# MPU6050.net
KiCad netlist of a schematic drawn in Altium Designer
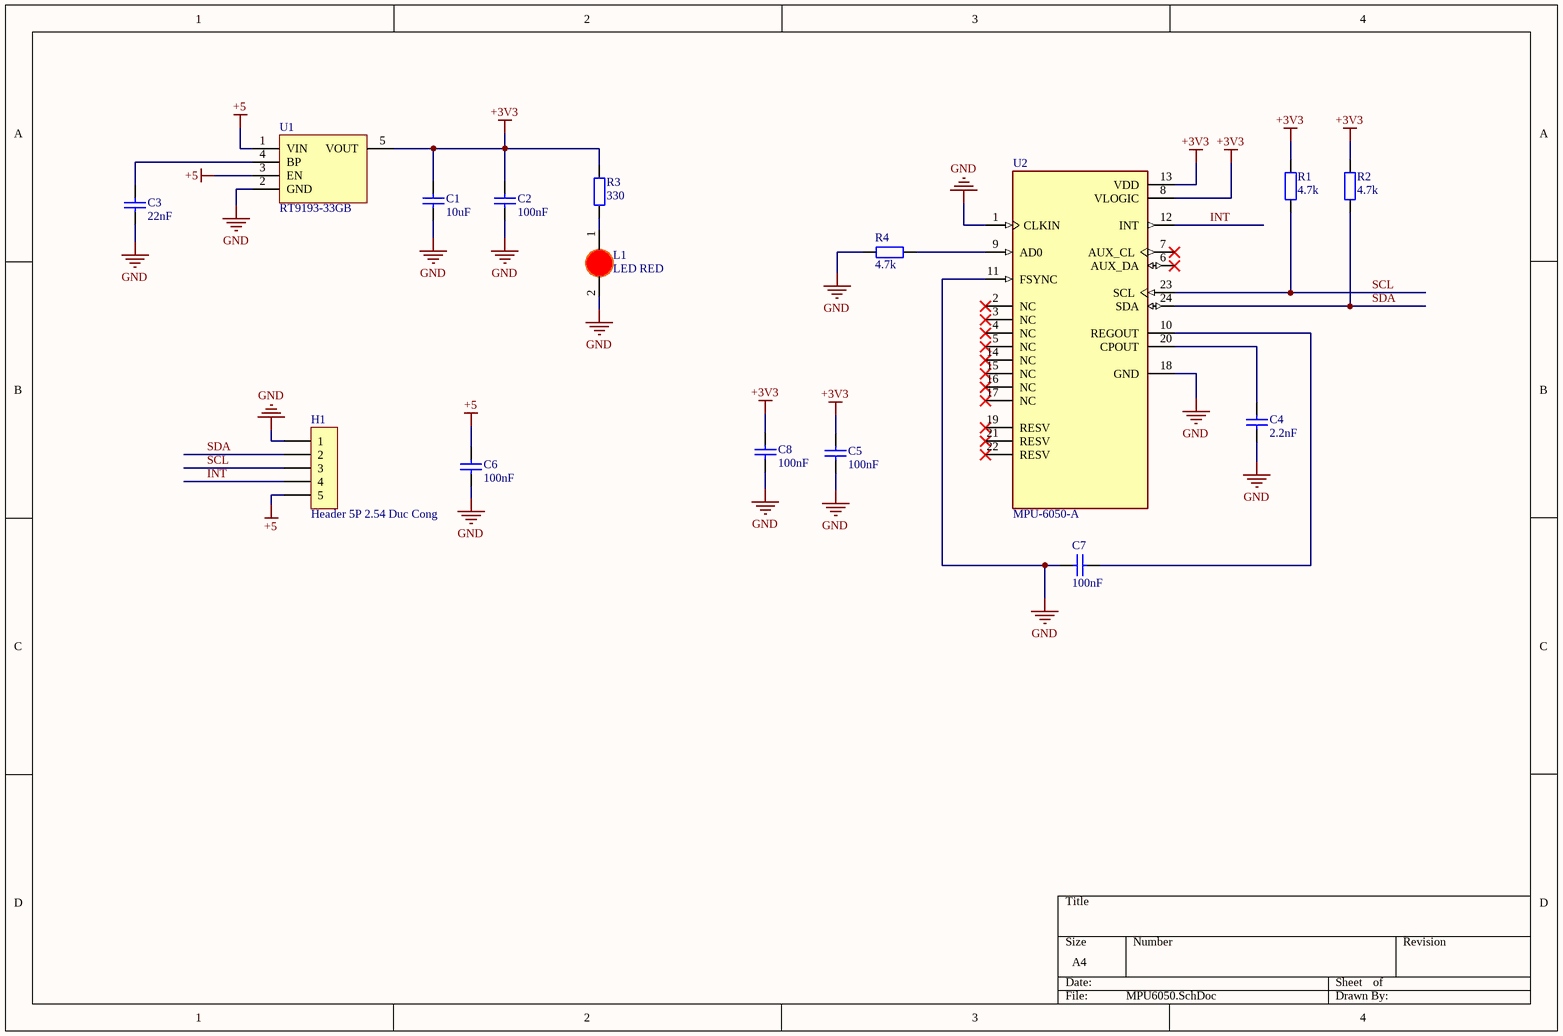
[diagram p0: MPU6050.SchDoc]

(export (version "E")
  (design (tool "Eeschema 10.0.6"))
  (components
    (comp (ref "C1")
      (value "10uF")
      (footprint "tu 0603")
      (description "Dán")
      (libsource (lib "namnt_Lib") (part "Tu 0603 106 16V 20%"))
    )
    (comp (ref "C2")
      (value "100nF")
      (footprint "tu 0603")
      (description "Dán")
      (libsource (lib "namnt_Lib") (part "Tu 0603 104 50V 10%"))
    )
    (comp (ref "C3")
      (value "22nF")
      (footprint "tu 0603")
      (description "Dán")
      (libsource (lib "namnt_Lib") (part "Tu 0603 104 50V 10%"))
    )
    (comp (ref "C4")
      (value "2.2nF")
      (footprint "tu 0603")
      (description "Dán")
      (libsource (lib "namnt_Lib") (part "Tu 0603 104 50V 10%"))
    )
    (comp (ref "C5")
      (value "100nF")
      (footprint "tu 0603")
      (description "Dán")
      (libsource (lib "namnt_Lib") (part "Tu 0603 104 50V 10%"))
    )
    (comp (ref "C6")
      (value "100nF")
      (footprint "tu 0603")
      (description "Dán")
      (libsource (lib "namnt_Lib") (part "Tu 0603 104 50V 10%"))
    )
    (comp (ref "C7")
      (value "100nF")
      (footprint "tu 0603")
      (description "Dán")
      (libsource (lib "namnt_Lib") (part "Tu 0603 104 50V 10%"))
    )
    (comp (ref "C8")
      (value "100nF")
      (footprint "tu 0603")
      (description "Dán")
      (libsource (lib "namnt_Lib") (part "Tu 0603 104 50V 10%"))
    )
    (comp (ref "H1")
      (value "Header 5P 2.54 Duc Cong")
      (footprint "Header 5P DC 2.54")
      (description "Cắm")
      (libsource (lib "namnt_Lib") (part "Header 5P 2.54 Duc Cong"))
    )
    (comp (ref "L1")
      (value "LED RED")
      (footprint "LED-0805-Red")
      (description "Dán")
      (libsource (lib "namnt_Lib") (part "LED 0805 Do"))
    )
    (comp (ref "R1")
      (value "4.7k")
      (footprint "tro smd 0603")
      (description "Dán")
      (libsource (lib "namnt_Lib") (part "Tro 0603 5% 4.7k"))
    )
    (comp (ref "R2")
      (value "4.7k")
      (footprint "tro smd 0603")
      (description "Dán")
      (libsource (lib "namnt_Lib") (part "Tro 0603 5% 4.7k"))
    )
    (comp (ref "R3")
      (value "330")
      (footprint "tro smd 0603")
      (description "Dán")
      (libsource (lib "namnt_Lib") (part "Tro 0603 1% 1k"))
    )
    (comp (ref "R4")
      (value "4.7k")
      (footprint "tro smd 0603")
      (description "Dán")
      (libsource (lib "namnt_Lib") (part "Tro 0603 5% 4.7k"))
    )
    (comp (ref "U1")
      (value "RT9193-33GB")
      (footprint "SOT23-5")
      (description "Linear Voltage Regulator IC 1 Output 300mA SOT-23-5")
      (fields (field (name "MANUFACTURER") "Richtek USA Inc."))
      (libsource (lib "namnt_Lib") (part "REG_5.5V-3.3V-0.3A-1W-SOT-23-5"))
    )
    (comp (ref "U2")
      (value "MPU-6050-A")
      (footprint "QFN50P400X400X95-24N")
      (fields (field (name "MF") "TDK InvenSense"))
      (libsource (lib "namnt_Lib") (part "MPU-6050-A"))
    )
  )
  (nets
    (net (code "1") (name "+3V3") (class "Default")
      (node (ref "C1") (pin "1") (pinfunction "1_1") (pintype "passive"))
      (node (ref "C2") (pin "1") (pinfunction "1_1") (pintype "passive"))
      (node (ref "C5") (pin "1") (pinfunction "1_1") (pintype "passive"))
      (node (ref "C8") (pin "1") (pinfunction "1_1") (pintype "passive"))
      (node (ref "R1") (pin "2") (pinfunction "2_2") (pintype "passive"))
      (node (ref "R2") (pin "2") (pinfunction "2_2") (pintype "passive"))
      (node (ref "R3") (pin "2") (pinfunction "2_2") (pintype "passive"))
      (node (ref "U1") (pin "5") (pinfunction "VOUT_5") (pintype "passive"))
      (node (ref "U2") (pin "13") (pinfunction "VDD_13") (pintype "power_in"))
      (node (ref "U2") (pin "8") (pinfunction "VLOGIC_8") (pintype "power_in"))
    )
    (net (code "2") (name "+5") (class "Default")
      (node (ref "C6") (pin "1") (pinfunction "1_1") (pintype "passive"))
      (node (ref "H1") (pin "5") (pinfunction "5_5") (pintype "passive"))
      (node (ref "U1") (pin "1") (pinfunction "VIN_1") (pintype "passive"))
      (node (ref "U1") (pin "3") (pinfunction "EN_3") (pintype "passive"))
    )
    (net (code "3") (name "/INT") (class "Default")
      (node (ref "H1") (pin "4") (pinfunction "4_4") (pintype "passive"))
      (node (ref "U2") (pin "12") (pinfunction "INT_12") (pintype "output"))
    )
    (net (code "4") (name "/SCL") (class "Default")
      (node (ref "H1") (pin "3") (pinfunction "3_3") (pintype "passive"))
      (node (ref "R1") (pin "1") (pinfunction "1_1") (pintype "passive"))
      (node (ref "U2") (pin "23") (pinfunction "SCL_23") (pintype "input"))
    )
    (net (code "5") (name "/SDA") (class "Default")
      (node (ref "H1") (pin "2") (pinfunction "2_2") (pintype "passive"))
      (node (ref "R2") (pin "1") (pinfunction "1_1") (pintype "passive"))
      (node (ref "U2") (pin "24") (pinfunction "SDA_24") (pintype "bidirectional"))
    )
    (net (code "6") (name "GND") (class "Default")
      (node (ref "C1") (pin "2") (pinfunction "2_2") (pintype "passive"))
      (node (ref "C2") (pin "2") (pinfunction "2_2") (pintype "passive"))
      (node (ref "C3") (pin "2") (pinfunction "2_2") (pintype "passive"))
      (node (ref "C4") (pin "2") (pinfunction "2_2") (pintype "passive"))
      (node (ref "C5") (pin "2") (pinfunction "2_2") (pintype "passive"))
      (node (ref "C6") (pin "2") (pinfunction "2_2") (pintype "passive"))
      (node (ref "C7") (pin "1") (pinfunction "1_1") (pintype "passive"))
      (node (ref "C8") (pin "2") (pinfunction "2_2") (pintype "passive"))
      (node (ref "H1") (pin "1") (pinfunction "1_1") (pintype "passive"))
      (node (ref "L1") (pin "2") (pinfunction "K_2") (pintype "passive"))
      (node (ref "R4") (pin "2") (pinfunction "2_2") (pintype "passive"))
      (node (ref "U1") (pin "2") (pinfunction "GND_2") (pintype "passive"))
      (node (ref "U2") (pin "1") (pinfunction "CLKIN_1") (pintype "input"))
      (node (ref "U2") (pin "11") (pinfunction "FSYNC_11") (pintype "input"))
      (node (ref "U2") (pin "18") (pinfunction "GND_18") (pintype "power_in"))
    )
    (net (code "7") (name "Net-(L1-A)") (class "Default")
      (node (ref "L1") (pin "1") (pinfunction "A_1") (pintype "passive"))
      (node (ref "R3") (pin "1") (pinfunction "1_1") (pintype "passive"))
    )
    (net (code "8") (name "Net-(U1-BP)") (class "Default")
      (node (ref "C3") (pin "1") (pinfunction "1_1") (pintype "passive"))
      (node (ref "U1") (pin "4") (pinfunction "BP_4") (pintype "passive"))
    )
    (net (code "9") (name "Net-(U2-AD0)") (class "Default")
      (node (ref "R4") (pin "1") (pinfunction "1_1") (pintype "passive"))
      (node (ref "U2") (pin "9") (pinfunction "AD0_9") (pintype "input"))
    )
    (net (code "10") (name "Net-(U2-CPOUT)") (class "Default")
      (node (ref "C4") (pin "1") (pinfunction "1_1") (pintype "passive"))
      (node (ref "U2") (pin "20") (pinfunction "CPOUT_20") (pintype "passive"))
    )
    (net (code "11") (name "Net-(U2-REGOUT)") (class "Default")
      (node (ref "C7") (pin "2") (pinfunction "2_2") (pintype "passive"))
      (node (ref "U2") (pin "10") (pinfunction "REGOUT_10") (pintype "passive"))
    )
    (net (code "12") (name "unconnected-(U2-AUX_CL-Pad7)") (class "Default")
      (node (ref "U2") (pin "7") (pinfunction "AUX_CL_7") (pintype "output+no_connect"))
    )
    (net (code "13") (name "unconnected-(U2-AUX_DA-Pad6)") (class "Default")
      (node (ref "U2") (pin "6") (pinfunction "AUX_DA_6") (pintype "bidirectional+no_connect"))
    )
    (net (code "14") (name "unconnected-(U2-NC-Pad2)") (class "Default")
      (node (ref "U2") (pin "2") (pinfunction "NC_2") (pintype "passive+no_connect"))
    )
    (net (code "15") (name "unconnected-(U2-NC-Pad3)") (class "Default")
      (node (ref "U2") (pin "3") (pinfunction "NC_3") (pintype "passive+no_connect"))
    )
    (net (code "16") (name "unconnected-(U2-NC-Pad4)") (class "Default")
      (node (ref "U2") (pin "4") (pinfunction "NC_4") (pintype "passive+no_connect"))
    )
    (net (code "17") (name "unconnected-(U2-NC-Pad5)") (class "Default")
      (node (ref "U2") (pin "5") (pinfunction "NC_5") (pintype "passive+no_connect"))
    )
    (net (code "18") (name "unconnected-(U2-NC-Pad14)") (class "Default")
      (node (ref "U2") (pin "14") (pinfunction "NC_14") (pintype "passive+no_connect"))
    )
    (net (code "19") (name "unconnected-(U2-NC-Pad15)") (class "Default")
      (node (ref "U2") (pin "15") (pinfunction "NC_15") (pintype "passive+no_connect"))
    )
    (net (code "20") (name "unconnected-(U2-NC-Pad16)") (class "Default")
      (node (ref "U2") (pin "16") (pinfunction "NC_16") (pintype "passive+no_connect"))
    )
    (net (code "21") (name "unconnected-(U2-NC-Pad17)") (class "Default")
      (node (ref "U2") (pin "17") (pinfunction "NC_17") (pintype "passive+no_connect"))
    )
    (net (code "22") (name "unconnected-(U2-RESV-Pad19)") (class "Default")
      (node (ref "U2") (pin "19") (pinfunction "RESV_19") (pintype "passive+no_connect"))
    )
    (net (code "23") (name "unconnected-(U2-RESV-Pad21)") (class "Default")
      (node (ref "U2") (pin "21") (pinfunction "RESV_21") (pintype "passive+no_connect"))
    )
    (net (code "24") (name "unconnected-(U2-RESV-Pad22)") (class "Default")
      (node (ref "U2") (pin "22") (pinfunction "RESV_22") (pintype "passive+no_connect"))
    )
  )
)
